# side_wide.net
KiCad netlist of a schematic drawn in EAGLE
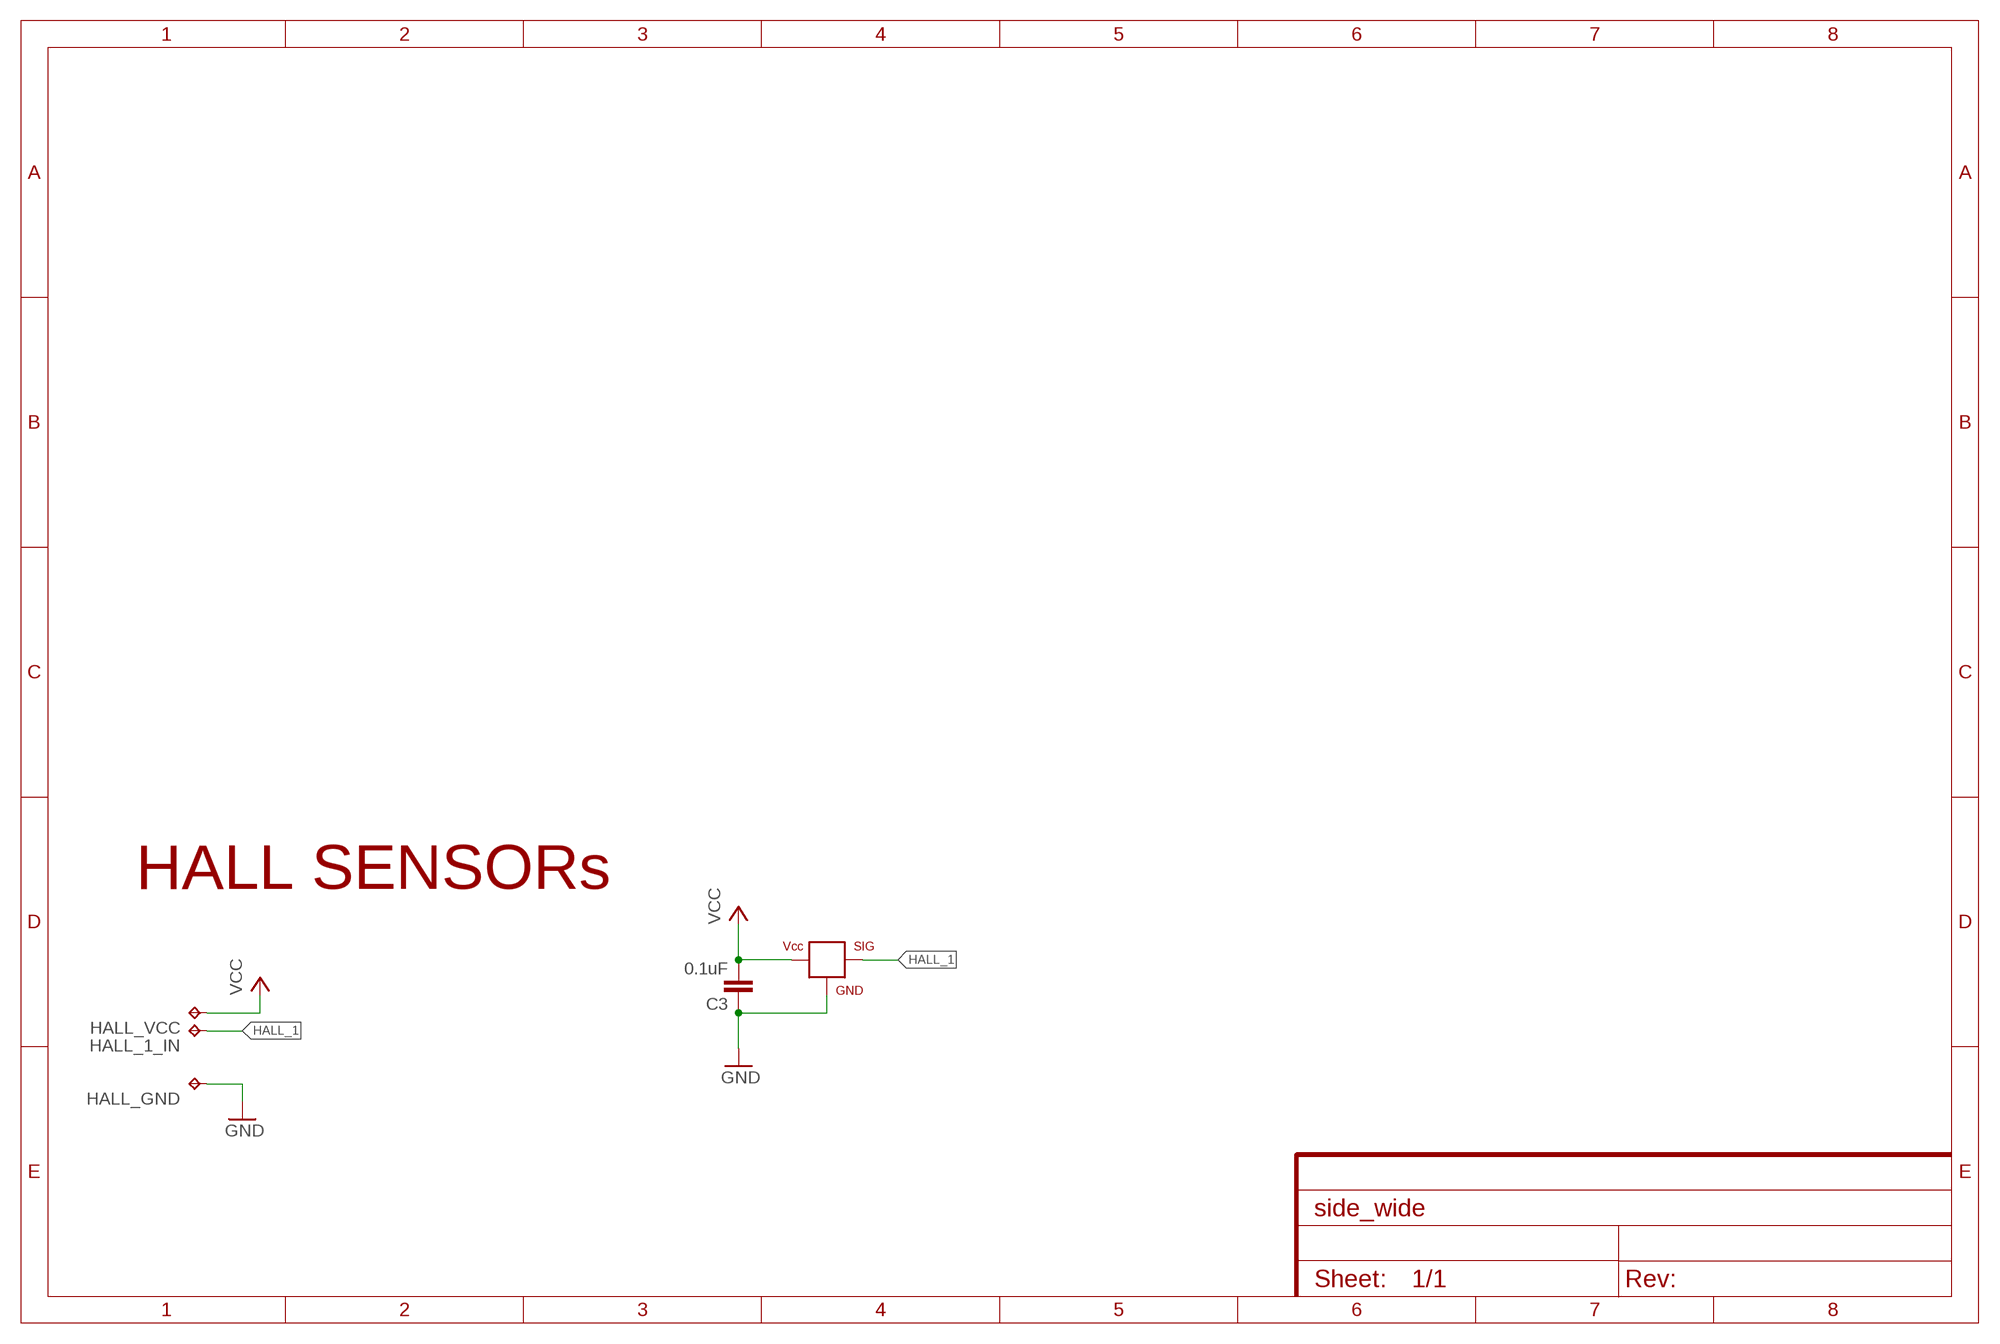
[diagram p0: schematic, sheet 1]

(export (version "E")
  (design (tool "Eeschema 10.0.6"))
  (components
    (comp (ref "C3")
      (value "0.1uF")
      (footprint "eagle-import:0603-CAP")
      (libsource (lib "eagle-import") (part "CAP0603-CAP"))
    )
    (comp (ref "HALL")
      (value "HALLEFFECT-A1326")
      (footprint "eagle-import:SOT23-3")
      (libsource (lib "eagle-import") (part "HALLEFFECT-A1326"))
    )
    (comp (ref "HALL_1_IN")
      (value "TPTP20SQ")
      (footprint "eagle-import:TP20SQ")
      (libsource (lib "eagle-import") (part "TPTP20SQ"))
    )
    (comp (ref "HALL_GND")
      (value "TPTP20SQ")
      (footprint "eagle-import:TP20SQ")
      (libsource (lib "eagle-import") (part "TPTP20SQ"))
    )
    (comp (ref "HALL_VCC")
      (value "TPTP20SQ")
      (footprint "eagle-import:TP20SQ")
      (libsource (lib "eagle-import") (part "TPTP20SQ"))
    )
  )
  (nets
    (net (code "1") (name "GND") (class "Default")
      (node (ref "C3") (pin "1") (pinfunction "1_1") (pintype "passive"))
      (node (ref "HALL") (pin "3") (pinfunction "GND_3") (pintype "bidirectional"))
      (node (ref "HALL_GND") (pin "TP") (pinfunction "TP_TP") (pintype "input"))
    )
    (net (code "2") (name "HALL_1") (class "Default")
      (node (ref "HALL") (pin "2") (pinfunction "SIG_2") (pintype "bidirectional"))
      (node (ref "HALL_1_IN") (pin "TP") (pinfunction "TP_TP") (pintype "input"))
    )
    (net (code "3") (name "VCC") (class "Default")
      (node (ref "C3") (pin "2") (pinfunction "2_2") (pintype "passive"))
      (node (ref "HALL") (pin "1") (pinfunction "VCC_1") (pintype "bidirectional"))
      (node (ref "HALL_VCC") (pin "TP") (pinfunction "TP_TP") (pintype "input"))
    )
  )
)
